# Sheet1.net
KiCad netlist of a schematic drawn in Altium Designer
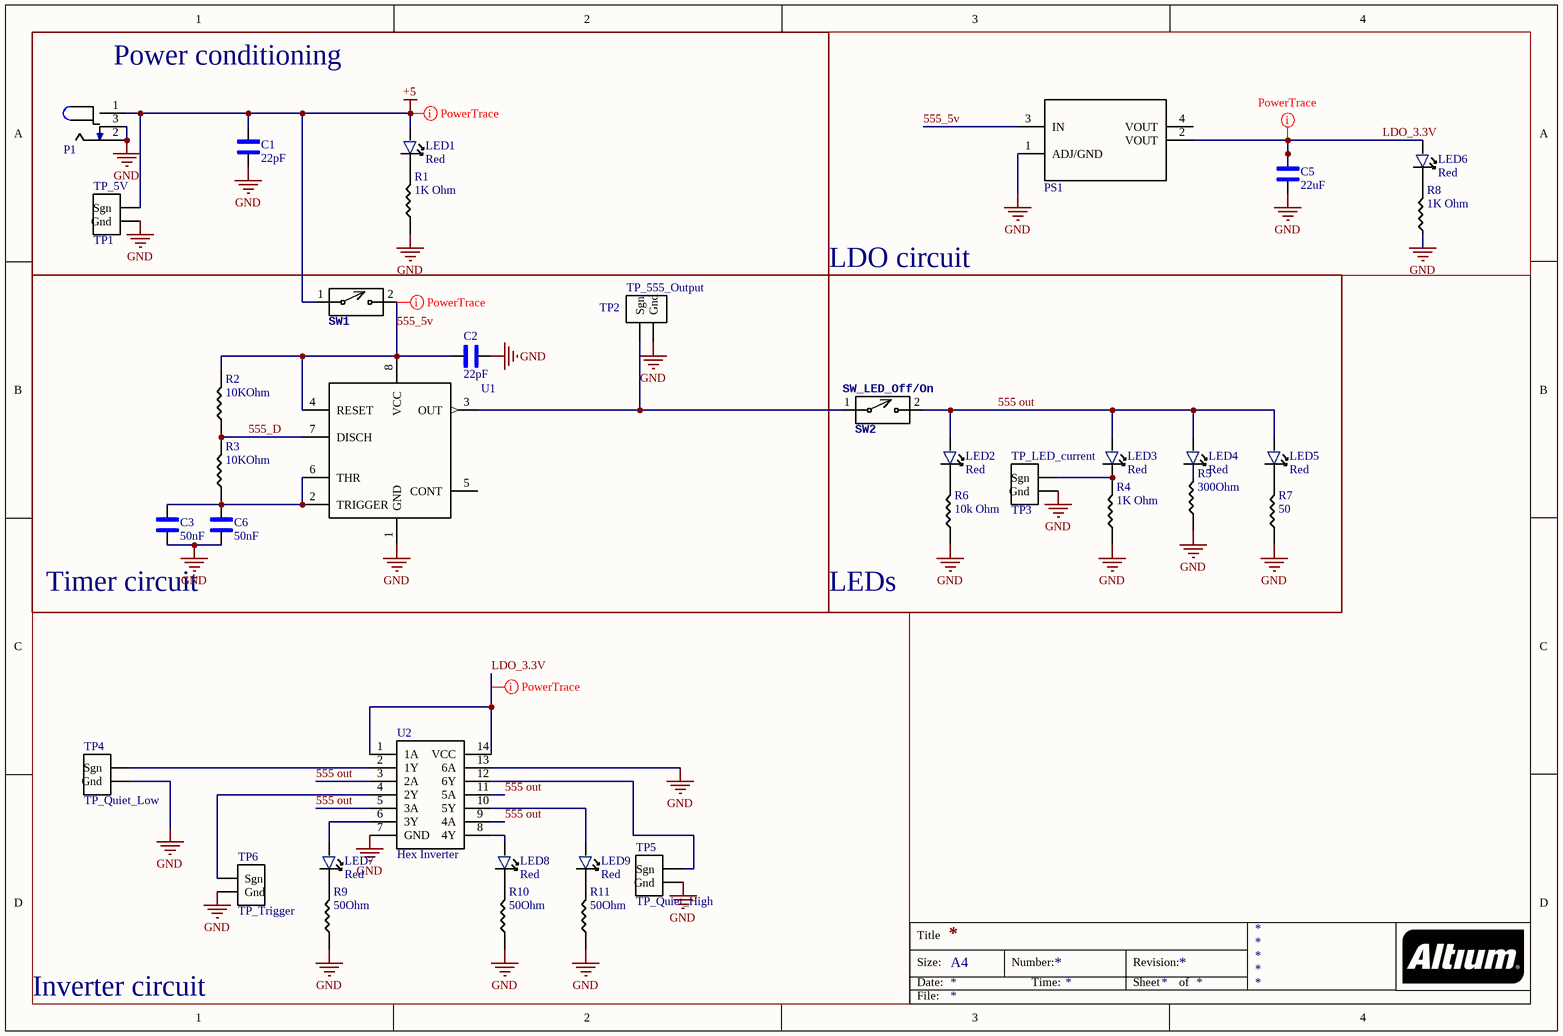
[diagram p0: Sheet1.SchDoc]

(export (version "E")
  (design (tool "Eeschema 10.0.6"))
  (components
    (comp (ref "C1")
      (value "22pF")
      (footprint "1206_Passive")
      (description "22pF ±5% 16V Ceramic Capacitor C0G, NP0 1206 (3216 Metric)")
      (fields (field (name "DIGIKEY PART") "732-7867-1-ND"))
      (libsource (lib "ECEN5730Lib_2020_08_AR") (part "C_22pF_1206"))
    )
    (comp (ref "C2")
      (value "22pF")
      (footprint "1206_Passive")
      (description "22pF ±5% 16V Ceramic Capacitor C0G, NP0 1206 (3216 Metric)")
      (fields (field (name "DIGIKEY PART") "732-7867-1-ND"))
      (libsource (lib "ECEN5730Lib_2020_08_AR") (part "C_22pF_1206"))
    )
    (comp (ref "C3")
      (value "50nF")
      (footprint "1206_Passive")
      (description "50nF ±5% 16V Ceramic Capacitor C0G, NP0 1206 (3216 Metric)")
      (fields (field (name "DIGIKEY PART") "732-7867-1-ND"))
      (libsource (lib "ECEN5730Lib_2020_08_AR (1)") (part "C_50nF_1206"))
    )
    (comp (ref "C5")
      (value "22uF")
      (footprint "1206_Passive")
      (description "22µF ±20% 16V Ceramic Capacitor X5R 1206 (3216 Metric)")
      (fields (field (name "DIGIKEY PART") "1276-2728-1-ND"))
      (libsource (lib "ECEN5730Lib_2020_08_AR (1)") (part "C_22uF_1206"))
    )
    (comp (ref "C6")
      (value "50nF")
      (footprint "1206_Passive")
      (description "50nF ±5% 16V Ceramic Capacitor C0G, NP0 1206 (3216 Metric)")
      (fields (field (name "DIGIKEY PART") "732-7867-1-ND"))
      (libsource (lib "ECEN5730Lib_2020_08_AR (1)") (part "C_50nF_1206"))
    )
    (comp (ref "LED1")
      (value "Red")
      (footprint "LED")
      (description "Red 638nm LED Indication - Discrete 1.8V 1206 (3216 Metric)")
      (fields (field (name "DIGIKEY PART") "160-1167-1-ND") (field (name "Comment") "LTST-C150CKT"))
      (libsource (lib "ECEN5730Lib_2020_08_AR") (part "LED_RED_1206"))
    )
    (comp (ref "LED2")
      (value "Red")
      (footprint "LED")
      (description "Red 638nm LED Indication - Discrete 1.8V 1206 (3216 Metric)")
      (fields (field (name "DIGIKEY PART") "160-1167-1-ND") (field (name "Comment") "LTST-C150CKT"))
      (libsource (lib "ECEN5730Lib_2020_08_AR") (part "LED_RED_1206"))
    )
    (comp (ref "LED3")
      (value "Red")
      (footprint "LED")
      (description "Red 638nm LED Indication - Discrete 1.8V 1206 (3216 Metric)")
      (fields (field (name "DIGIKEY PART") "160-1167-1-ND") (field (name "Comment") "LTST-C150CKT"))
      (libsource (lib "ECEN5730Lib_2020_08_AR") (part "LED_RED_1206"))
    )
    (comp (ref "LED4")
      (value "Red")
      (footprint "LED")
      (description "Red 638nm LED Indication - Discrete 1.8V 1206 (3216 Metric)")
      (fields (field (name "DIGIKEY PART") "160-1167-1-ND") (field (name "Comment") "LTST-C150CKT"))
      (libsource (lib "ECEN5730Lib_2020_08_AR") (part "LED_RED_1206"))
    )
    (comp (ref "LED5")
      (value "Red")
      (footprint "LED")
      (description "Red 638nm LED Indication - Discrete 1.8V 1206 (3216 Metric)")
      (fields (field (name "DIGIKEY PART") "160-1167-1-ND") (field (name "Comment") "LTST-C150CKT"))
      (libsource (lib "ECEN5730Lib_2020_08_AR") (part "LED_RED_1206"))
    )
    (comp (ref "LED6")
      (value "Red")
      (footprint "LED")
      (description "Red 638nm LED Indication - Discrete 1.8V 1206 (3216 Metric)")
      (fields (field (name "DIGIKEY PART") "160-1167-1-ND") (field (name "Comment") "LTST-C150CKT"))
      (libsource (lib "ECEN5730Lib_2020_08_AR") (part "LED_RED_1206"))
    )
    (comp (ref "LED7")
      (value "Red")
      (footprint "LED")
      (description "Red 638nm LED Indication - Discrete 1.8V 1206 (3216 Metric)")
      (fields (field (name "DIGIKEY PART") "160-1167-1-ND") (field (name "Comment") "LTST-C150CKT"))
      (libsource (lib "ECEN5730Lib_2020_08_AR") (part "LED_RED_1206"))
    )
    (comp (ref "LED8")
      (value "Red")
      (footprint "LED")
      (description "Red 638nm LED Indication - Discrete 1.8V 1206 (3216 Metric)")
      (fields (field (name "DIGIKEY PART") "160-1167-1-ND") (field (name "Comment") "LTST-C150CKT"))
      (libsource (lib "ECEN5730Lib_2020_08_AR") (part "LED_RED_1206"))
    )
    (comp (ref "LED9")
      (value "Red")
      (footprint "LED")
      (description "Red 638nm LED Indication - Discrete 1.8V 1206 (3216 Metric)")
      (fields (field (name "DIGIKEY PART") "160-1167-1-ND") (field (name "Comment") "LTST-C150CKT"))
      (libsource (lib "ECEN5730Lib_2020_08_AR") (part "LED_RED_1206"))
    )
    (comp (ref "P1")
      (value "Power Jack")
      (footprint "Power_Jack")
      (description "Power Barrel Connector Jack 2.10mm ID (0.083\"), 5.50mm OD (0.217\") Through Hole, Right Angle")
      (fields (field (name "DIGIKEY PART") "CP-102A-ND"))
      (libsource (lib "ECEN5730Lib_2020_08_AR") (part "P_Power Jack"))
    )
    (comp (ref "PS1")
      (value "AZ1117CH-3.3TRG1")
      (footprint "LDO")
      (description "Linear Voltage Regulator IC Positive Fixed 1 Output 1A SOT-223")
      (fields (field (name "DIGIKEY PART") "AZ1117CH-3.3TRG1DICT-ND"))
      (libsource (lib "ECEN5730Lib_2020_08_AR (1)") (part "PS_LDO_3v3"))
    )
    (comp (ref "R1")
      (value "1K Ohm")
      (footprint "1206_Passive")
      (description "1 kOhms ±1% 0.5W, 1/2W Chip Resistor 1206 (3216 Metric) Anti-Sulfur, Moisture Resistant Thin Film")
      (fields (field (name "DIGIKEY PART") "RNCP1206FTD1K00CT-ND") (field (name "Comment") "1k"))
      (libsource (lib "ECEN5730Lib_2020_08_AR") (part "R_1K_1206"))
    )
    (comp (ref "R2")
      (value "10KOhm")
      (footprint "1206_Passive")
      (description "10 kOhms ±5% 0.25W, 1/4W Chip Resistor 1206 (3216 Metric) Automotive AEC-Q200 Thick Film")
      (fields (field (name "DIGIKEY PART") "RMCF1206JT300RCT-ND") (field (name "Comment") "10k"))
      (libsource (lib "ECEN5730Lib_2020_08_AR (1)") (part "R_10KOhm_1206"))
    )
    (comp (ref "R3")
      (value "10KOhm")
      (footprint "1206_Passive")
      (description "10 kOhms ±5% 0.25W, 1/4W Chip Resistor 1206 (3216 Metric) Automotive AEC-Q200 Thick Film")
      (fields (field (name "DIGIKEY PART") "RMCF1206JT300RCT-ND") (field (name "Comment") "10k"))
      (libsource (lib "ECEN5730Lib_2020_08_AR (1)") (part "R_10KOhm_1206"))
    )
    (comp (ref "R4")
      (value "1K Ohm")
      (footprint "1206_Passive")
      (description "1 kOhms ±1% 0.5W, 1/2W Chip Resistor 1206 (3216 Metric) Anti-Sulfur, Moisture Resistant Thin Film")
      (fields (field (name "DIGIKEY PART") "RNCP1206FTD1K00CT-ND") (field (name "Comment") "1k"))
      (libsource (lib "ECEN5730Lib_2020_08_AR") (part "R_1K_1206"))
    )
    (comp (ref "R5")
      (value "300Ohm")
      (footprint "1206_Passive")
      (description "300 Ohms ±5% 0.25W, 1/4W Chip Resistor 1206 (3216 Metric) Automotive AEC-Q200 Thick Film")
      (fields (field (name "DIGIKEY PART") "RMCF1206JT300RCT-ND") (field (name "Comment") "300"))
      (libsource (lib "ECEN5730Lib_2020_08_AR") (part "R_300Ohm_1206"))
    )
    (comp (ref "R6")
      (value "10k Ohm")
      (footprint "1206_Passive")
      (description "1 MOhms ±5% 0.25W, 1/4W Chip Resistor 1206 (3216 Metric) Automotive AEC-Q200 Thick Film")
      (fields (field (name "DIGIKEY PART") "Number RMCF1206JT1M00CT-ND") (field (name "Comment") "1M"))
      (libsource (lib "ECEN5730Lib_2020_08_AR") (part "R_1M_1206"))
    )
    (comp (ref "R7")
      (value "50")
      (footprint "1206_Passive")
      (description "1 MOhms ±5% 0.25W, 1/4W Chip Resistor 1206 (3216 Metric) Automotive AEC-Q200 Thick Film")
      (fields (field (name "DIGIKEY PART") "Number RMCF1206JT1M00CT-ND") (field (name "Comment") "1M"))
      (libsource (lib "ECEN5730Lib_2020_08_AR") (part "R_1M_1206"))
    )
    (comp (ref "R8")
      (value "1K Ohm")
      (footprint "1206_Passive")
      (description "1 kOhms ±1% 0.5W, 1/2W Chip Resistor 1206 (3216 Metric) Anti-Sulfur, Moisture Resistant Thin Film")
      (fields (field (name "DIGIKEY PART") "RNCP1206FTD1K00CT-ND") (field (name "Comment") "1k"))
      (libsource (lib "ECEN5730Lib_2020_08_AR") (part "R_1K_1206"))
    )
    (comp (ref "R9")
      (value "50Ohm")
      (footprint "1206_Passive")
      (description "50 Ohms ±5% 0.25W, 1/4W Chip Resistor 1206 (3216 Metric) Automotive AEC-Q200 Thick Film")
      (fields (field (name "DIGIKEY PART") "RMCF1206JT300RCT-ND") (field (name "Comment") "50"))
      (libsource (lib "ECEN5730Lib_2020_08_AR (1)") (part "R_50Ohm_1206"))
    )
    (comp (ref "R10")
      (value "50Ohm")
      (footprint "1206_Passive")
      (description "50 Ohms ±5% 0.25W, 1/4W Chip Resistor 1206 (3216 Metric) Automotive AEC-Q200 Thick Film")
      (fields (field (name "DIGIKEY PART") "RMCF1206JT300RCT-ND") (field (name "Comment") "50"))
      (libsource (lib "ECEN5730Lib_2020_08_AR (1)") (part "R_50Ohm_1206"))
    )
    (comp (ref "R11")
      (value "50Ohm")
      (footprint "1206_Passive")
      (description "50 Ohms ±5% 0.25W, 1/4W Chip Resistor 1206 (3216 Metric) Automotive AEC-Q200 Thick Film")
      (fields (field (name "DIGIKEY PART") "RMCF1206JT300RCT-ND") (field (name "Comment") "50"))
      (libsource (lib "ECEN5730Lib_2020_08_AR (1)") (part "R_50Ohm_1206"))
    )
    (comp (ref "SW1")
      (value "SW_2Pin_100mil_Switch")
      (footprint "2Pin-Header-Conn")
      (description "2Pin Header")
      (libsource (lib "ECEN5730Lib_2020_08_AR") (part "SW_2Pin_100mil_Switch"))
    )
    (comp (ref "SW2")
      (value "SW_LED_Off/On")
      (footprint "2Pin-Header-Conn")
      (description "2Pin Header")
      (libsource (lib "ECEN5730Lib_2020_08_AR") (part "SW_2Pin_100mil_Switch"))
    )
    (comp (ref "TP1")
      (value "TP_5V")
      (footprint "TP10x_Probe")
      (description "Test Point 300 mil centers")
      (libsource (lib "") (part "TP_10x_Probe_2"))
    )
    (comp (ref "TP2")
      (value "TP_555_Output")
      (footprint "TP10x_Probe")
      (description "Test Point 300 mil centers")
      (libsource (lib "ECEN5730Lib_2020_08_AR") (part "TP_10x_Probe"))
    )
    (comp (ref "TP3")
      (value "TP_LED_current")
      (footprint "TP10x_Probe")
      (description "Test Point 300 mil centers")
      (libsource (lib "") (part "TP_10x_Probe_2"))
    )
    (comp (ref "TP4")
      (value "TP_Quiet_Low")
      (footprint "TP10x_Probe")
      (description "Test Point 300 mil centers")
      (libsource (lib "") (part "TP_10x_Probe_2"))
    )
    (comp (ref "TP5")
      (value "TP_Quiet_High")
      (footprint "TP10x_Probe")
      (description "Test Point 300 mil centers")
      (libsource (lib "") (part "TP_10x_Probe_2"))
    )
    (comp (ref "TP6")
      (value "TP_Trigger")
      (footprint "TP10x_Probe")
      (description "Test Point 300 mil centers")
      (libsource (lib "") (part "TP_10x_Probe_1"))
    )
    (comp (ref "U1")
      (value "U_555_Fast")
      (footprint "TS555IDTTR")
      (description "555 Type, Timer/Oscillator _Single_ IC 2.7MHz 8-SO")
      (fields (field (name "MP") "TS555IDTTR") (field (name "MF") "STMicroelectronics"))
      (libsource (lib "ECEN5730Lib_2020_08_AR") (part "U_555_Fast"))
    )
    (comp (ref "U2")
      (value "Hex Inverter")
      (footprint "HEX_74LVT14D")
      (description "Inverter IC 6 Channel Schmitt Trigger 14-SOIC")
      (libsource (lib "ECEN5730Lib_2020_08_AR (1)") (part "U_7414_LVTD_Hex"))
    )
  )
  (nets
    (net (code "1") (name "+5") (class "Default")
      (node (ref "C1") (pin "1") (pinfunction "1_1") (pintype "passive"))
      (node (ref "LED1") (pin "2") (pinfunction "2_2") (pintype "passive"))
      (node (ref "P1") (pin "1") (pinfunction "1_1") (pintype "power_in"))
      (node (ref "SW1") (pin "1") (pinfunction "1_1") (pintype "passive"))
      (node (ref "TP1") (pin "1") (pinfunction "Sgn_1") (pintype "passive"))
    )
    (net (code "2") (name "/555 out") (class "Default")
      (node (ref "LED2") (pin "2") (pinfunction "2_2") (pintype "passive"))
      (node (ref "LED3") (pin "2") (pinfunction "2_2") (pintype "passive"))
      (node (ref "LED4") (pin "2") (pinfunction "2_2") (pintype "passive"))
      (node (ref "LED5") (pin "2") (pinfunction "2_2") (pintype "passive"))
      (node (ref "SW2") (pin "2") (pinfunction "2_2") (pintype "passive"))
      (node (ref "U2") (pin "11") (pinfunction "5A_11") (pintype "passive"))
      (node (ref "U2") (pin "3") (pinfunction "2A_3") (pintype "passive"))
      (node (ref "U2") (pin "5") (pinfunction "3A_5") (pintype "passive"))
      (node (ref "U2") (pin "9") (pinfunction "4A_9") (pintype "passive"))
    )
    (net (code "3") (name "/555_5v") (class "Default")
      (node (ref "C2") (pin "2") (pinfunction "2_2") (pintype "passive"))
      (node (ref "PS1") (pin "3") (pinfunction "IN_3") (pintype "power_in"))
      (node (ref "R2") (pin "2") (pinfunction "2_2") (pintype "passive"))
      (node (ref "SW1") (pin "2") (pinfunction "2_2") (pintype "passive"))
      (node (ref "U1") (pin "4") (pinfunction "RESET_4") (pintype "passive"))
      (node (ref "U1") (pin "8") (pinfunction "VCC_8") (pintype "power_in"))
    )
    (net (code "4") (name "/555_D") (class "Default")
      (node (ref "R2") (pin "1") (pinfunction "1_1") (pintype "passive"))
      (node (ref "R3") (pin "2") (pinfunction "2_2") (pintype "passive"))
      (node (ref "U1") (pin "7") (pinfunction "DISCH_7") (pintype "passive"))
    )
    (net (code "5") (name "/LDO_3.3V") (class "Default")
      (node (ref "C5") (pin "2") (pinfunction "2_2") (pintype "passive"))
      (node (ref "LED6") (pin "2") (pinfunction "2_2") (pintype "passive"))
      (node (ref "PS1") (pin "2") (pinfunction "VOUT_2") (pintype "power_in"))
      (node (ref "U2") (pin "1") (pinfunction "1A_1") (pintype "passive"))
      (node (ref "U2") (pin "14") (pinfunction "VCC_14") (pintype "passive"))
    )
    (net (code "6") (name "GND") (class "Default")
      (node (ref "C1") (pin "2") (pinfunction "2_2") (pintype "passive"))
      (node (ref "C2") (pin "1") (pinfunction "1_1") (pintype "passive"))
      (node (ref "C3") (pin "1") (pinfunction "1_1") (pintype "passive"))
      (node (ref "C5") (pin "1") (pinfunction "1_1") (pintype "passive"))
      (node (ref "C6") (pin "1") (pinfunction "1_1") (pintype "passive"))
      (node (ref "P1") (pin "2") (pinfunction "2_2") (pintype "power_in"))
      (node (ref "P1") (pin "3") (pinfunction "3_3") (pintype "power_in"))
      (node (ref "PS1") (pin "1") (pinfunction "ADJ/GND_1") (pintype "passive"))
      (node (ref "R1") (pin "1") (pinfunction "1_1") (pintype "passive"))
      (node (ref "R10") (pin "1") (pinfunction "1_1") (pintype "passive"))
      (node (ref "R11") (pin "1") (pinfunction "1_1") (pintype "passive"))
      (node (ref "R4") (pin "1") (pinfunction "1_1") (pintype "passive"))
      (node (ref "R5") (pin "1") (pinfunction "1_1") (pintype "passive"))
      (node (ref "R6") (pin "1") (pinfunction "1_1") (pintype "passive"))
      (node (ref "R7") (pin "1") (pinfunction "1_1") (pintype "passive"))
      (node (ref "R8") (pin "1") (pinfunction "1_1") (pintype "passive"))
      (node (ref "R9") (pin "1") (pinfunction "1_1") (pintype "passive"))
      (node (ref "TP1") (pin "2") (pinfunction "Gnd_2") (pintype "passive"))
      (node (ref "TP2") (pin "2") (pinfunction "Gnd_2") (pintype "passive"))
      (node (ref "TP3") (pin "2") (pinfunction "Gnd_2") (pintype "passive"))
      (node (ref "TP4") (pin "2") (pinfunction "Gnd_2") (pintype "passive"))
      (node (ref "TP5") (pin "2") (pinfunction "Gnd_2") (pintype "passive"))
      (node (ref "TP6") (pin "2") (pinfunction "Gnd_2") (pintype "passive"))
      (node (ref "U1") (pin "1") (pinfunction "GND_1") (pintype "power_in"))
      (node (ref "U2") (pin "13") (pinfunction "6A_13") (pintype "passive"))
      (node (ref "U2") (pin "7") (pinfunction "GND_7") (pintype "passive"))
    )
    (net (code "7") (name "Net-(LED1-Pad1)") (class "Default")
      (node (ref "LED1") (pin "1") (pinfunction "1_1") (pintype "passive"))
      (node (ref "R1") (pin "2") (pinfunction "2_2") (pintype "passive"))
    )
    (net (code "8") (name "Net-(LED2-Pad1)") (class "Default")
      (node (ref "LED2") (pin "1") (pinfunction "1_1") (pintype "passive"))
      (node (ref "R6") (pin "2") (pinfunction "2_2") (pintype "passive"))
    )
    (net (code "9") (name "Net-(LED4-Pad1)") (class "Default")
      (node (ref "LED4") (pin "1") (pinfunction "1_1") (pintype "passive"))
      (node (ref "R5") (pin "2") (pinfunction "2_2") (pintype "passive"))
    )
    (net (code "10") (name "Net-(LED5-Pad1)") (class "Default")
      (node (ref "LED5") (pin "1") (pinfunction "1_1") (pintype "passive"))
      (node (ref "R7") (pin "2") (pinfunction "2_2") (pintype "passive"))
    )
    (net (code "11") (name "Net-(LED6-Pad1)") (class "Default")
      (node (ref "LED6") (pin "1") (pinfunction "1_1") (pintype "passive"))
      (node (ref "R8") (pin "2") (pinfunction "2_2") (pintype "passive"))
    )
    (net (code "12") (name "Net-(LED7-Pad1)") (class "Default")
      (node (ref "LED7") (pin "1") (pinfunction "1_1") (pintype "passive"))
      (node (ref "R9") (pin "2") (pinfunction "2_2") (pintype "passive"))
    )
    (net (code "13") (name "Net-(LED8-Pad1)") (class "Default")
      (node (ref "LED8") (pin "1") (pinfunction "1_1") (pintype "passive"))
      (node (ref "R10") (pin "2") (pinfunction "2_2") (pintype "passive"))
    )
    (net (code "14") (name "Net-(LED9-Pad1)") (class "Default")
      (node (ref "LED9") (pin "1") (pinfunction "1_1") (pintype "passive"))
      (node (ref "R11") (pin "2") (pinfunction "2_2") (pintype "passive"))
    )
    (net (code "15") (name "Net-(TP2-Sgn)") (class "Default")
      (node (ref "SW2") (pin "1") (pinfunction "1_1") (pintype "passive"))
      (node (ref "TP2") (pin "1") (pinfunction "Sgn_1") (pintype "passive"))
      (node (ref "U1") (pin "3") (pinfunction "OUT_3") (pintype "output"))
    )
    (net (code "16") (name "Net-(TP3-Sgn)") (class "Default")
      (node (ref "LED3") (pin "1") (pinfunction "1_1") (pintype "passive"))
      (node (ref "R4") (pin "2") (pinfunction "2_2") (pintype "passive"))
      (node (ref "TP3") (pin "1") (pinfunction "Sgn_1") (pintype "passive"))
    )
    (net (code "17") (name "Net-(TP4-Sgn)") (class "Default")
      (node (ref "TP4") (pin "1") (pinfunction "Sgn_1") (pintype "passive"))
      (node (ref "U2") (pin "2") (pinfunction "1Y_2") (pintype "passive"))
    )
    (net (code "18") (name "Net-(TP5-Sgn)") (class "Default")
      (node (ref "TP5") (pin "1") (pinfunction "Sgn_1") (pintype "passive"))
      (node (ref "U2") (pin "12") (pinfunction "6Y_12") (pintype "passive"))
    )
    (net (code "19") (name "Net-(TP6-Sgn)") (class "Default")
      (node (ref "TP6") (pin "1") (pinfunction "Sgn_1") (pintype "passive"))
      (node (ref "U2") (pin "4") (pinfunction "2Y_4") (pintype "passive"))
    )
    (net (code "20") (name "Net-(U1-THR)") (class "Default")
      (node (ref "C3") (pin "2") (pinfunction "2_2") (pintype "passive"))
      (node (ref "C6") (pin "2") (pinfunction "2_2") (pintype "passive"))
      (node (ref "R3") (pin "1") (pinfunction "1_1") (pintype "passive"))
      (node (ref "U1") (pin "2") (pinfunction "TRIGGER_2") (pintype "passive"))
      (node (ref "U1") (pin "6") (pinfunction "THR_6") (pintype "passive"))
    )
    (net (code "21") (name "Net-(U2-3Y)") (class "Default")
      (node (ref "LED7") (pin "2") (pinfunction "2_2") (pintype "passive"))
      (node (ref "U2") (pin "6") (pinfunction "3Y_6") (pintype "passive"))
    )
    (net (code "22") (name "Net-(U2-4Y)") (class "Default")
      (node (ref "LED8") (pin "2") (pinfunction "2_2") (pintype "passive"))
      (node (ref "U2") (pin "8") (pinfunction "4Y_8") (pintype "passive"))
    )
    (net (code "23") (name "Net-(U2-5Y)") (class "Default")
      (node (ref "LED9") (pin "2") (pinfunction "2_2") (pintype "passive"))
      (node (ref "U2") (pin "10") (pinfunction "5Y_10") (pintype "passive"))
    )
    (net (code "24") (name "unconnected-(PS1-VOUT-Pad4)") (class "Default")
      (node (ref "PS1") (pin "4") (pinfunction "VOUT_4") (pintype "power_in"))
    )
    (net (code "25") (name "unconnected-(U1-CONT-Pad5)") (class "Default")
      (node (ref "U1") (pin "5") (pinfunction "CONT_5") (pintype "passive"))
    )
  )
)
